# PCIE.net
KiCad netlist of a schematic drawn in Altium Designer
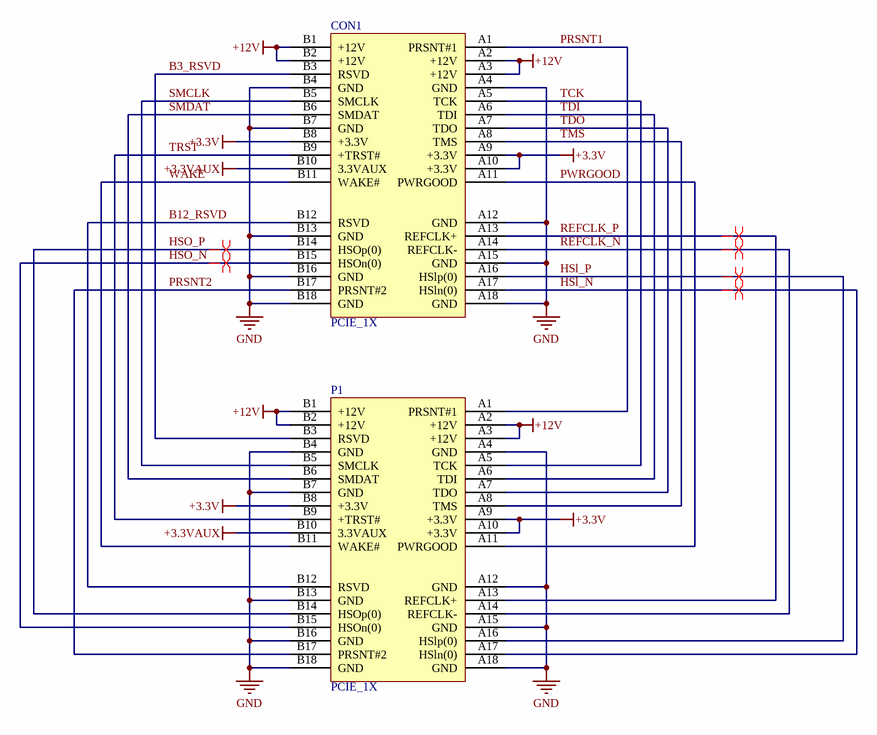
[diagram p0: PCIE.SchDoc]

(export (version "E")
  (design (tool "Eeschema 10.0.6"))
  (components
    (comp (ref "CON1") (value "PCIE_1X") (footprint "PCIE_1X_EDGE") (libsource (lib "PCIE") (part "PCIE_1X")))
    (comp (ref "P1") (value "PCIE_1X") (footprint "NWE18DHHN-T931") (libsource (lib "PCIE") (part "PCIE_1X")))
  )
  (nets
    (net (code "1") (name "+3.3V") (class "Default")
      (node (ref "CON1") (pin "A10") (pinfunction "+3.3V_A10") (pintype "power_in"))
      (node (ref "CON1") (pin "A9") (pinfunction "+3.3V_A9") (pintype "power_in"))
      (node (ref "CON1") (pin "B8") (pinfunction "+3.3V_B8") (pintype "power_in"))
      (node (ref "P1") (pin "A10") (pinfunction "+3.3V_A10") (pintype "power_in"))
      (node (ref "P1") (pin "A9") (pinfunction "+3.3V_A9") (pintype "power_in"))
      (node (ref "P1") (pin "B8") (pinfunction "+3.3V_B8") (pintype "power_in"))
    )
    (net (code "2") (name "+3.3VAUX") (class "Default")
      (node (ref "CON1") (pin "B10") (pinfunction "3.3VAUX_B10") (pintype "power_in"))
      (node (ref "P1") (pin "B10") (pinfunction "3.3VAUX_B10") (pintype "power_in"))
    )
    (net (code "3") (name "+12V") (class "Default")
      (node (ref "CON1") (pin "A2") (pinfunction "+12V_A2") (pintype "power_in"))
      (node (ref "CON1") (pin "A3") (pinfunction "+12V_A3") (pintype "power_in"))
      (node (ref "CON1") (pin "B1") (pinfunction "+12V_B1") (pintype "power_in"))
      (node (ref "CON1") (pin "B2") (pinfunction "+12V_B2") (pintype "power_in"))
      (node (ref "P1") (pin "A2") (pinfunction "+12V_A2") (pintype "power_in"))
      (node (ref "P1") (pin "A3") (pinfunction "+12V_A3") (pintype "power_in"))
      (node (ref "P1") (pin "B1") (pinfunction "+12V_B1") (pintype "power_in"))
      (node (ref "P1") (pin "B2") (pinfunction "+12V_B2") (pintype "power_in"))
    )
    (net (code "4") (name "/B3_RSVD") (class "Default")
      (node (ref "CON1") (pin "B3") (pinfunction "RSVD_B3") (pintype "power_in"))
      (node (ref "P1") (pin "B3") (pinfunction "RSVD_B3") (pintype "power_in"))
    )
    (net (code "5") (name "/B12_RSVD") (class "Default")
      (node (ref "CON1") (pin "B12") (pinfunction "RSVD_B12") (pintype "power_in"))
      (node (ref "P1") (pin "B12") (pinfunction "RSVD_B12") (pintype "power_in"))
    )
    (net (code "6") (name "/HSO_N") (class "Default")
      (node (ref "CON1") (pin "B15") (pinfunction "HSOn(0)_B15") (pintype "power_in"))
      (node (ref "P1") (pin "B15") (pinfunction "HSOn(0)_B15") (pintype "power_in"))
    )
    (net (code "7") (name "/HSO_P") (class "Default")
      (node (ref "CON1") (pin "B14") (pinfunction "HSOp(0)_B14") (pintype "power_in"))
      (node (ref "P1") (pin "B14") (pinfunction "HSOp(0)_B14") (pintype "power_in"))
    )
    (net (code "8") (name "/HSl_N") (class "Default")
      (node (ref "CON1") (pin "A17") (pinfunction "HSln(0)_A17") (pintype "power_in"))
      (node (ref "P1") (pin "A17") (pinfunction "HSln(0)_A17") (pintype "power_in"))
    )
    (net (code "9") (name "/HSl_P") (class "Default")
      (node (ref "CON1") (pin "A16") (pinfunction "HSlp(0)_A16") (pintype "power_in"))
      (node (ref "P1") (pin "A16") (pinfunction "HSlp(0)_A16") (pintype "power_in"))
    )
    (net (code "10") (name "/PRSNT1") (class "Default")
      (node (ref "CON1") (pin "A1") (pinfunction "PRSNT#1_A1") (pintype "power_in"))
      (node (ref "P1") (pin "A1") (pinfunction "PRSNT#1_A1") (pintype "power_in"))
    )
    (net (code "11") (name "/PRSNT2") (class "Default")
      (node (ref "CON1") (pin "B17") (pinfunction "PRSNT#2_B17") (pintype "power_in"))
      (node (ref "P1") (pin "B17") (pinfunction "PRSNT#2_B17") (pintype "power_in"))
    )
    (net (code "12") (name "/PWRGOOD") (class "Default")
      (node (ref "CON1") (pin "A11") (pinfunction "PWRGOOD_A11") (pintype "power_in"))
      (node (ref "P1") (pin "A11") (pinfunction "PWRGOOD_A11") (pintype "power_in"))
    )
    (net (code "13") (name "/REFCLK_N") (class "Default")
      (node (ref "CON1") (pin "A14") (pinfunction "REFCLK-_A14") (pintype "power_in"))
      (node (ref "P1") (pin "A14") (pinfunction "REFCLK-_A14") (pintype "power_in"))
    )
    (net (code "14") (name "/REFCLK_P") (class "Default")
      (node (ref "CON1") (pin "A13") (pinfunction "REFCLK+_A13") (pintype "power_in"))
      (node (ref "P1") (pin "A13") (pinfunction "REFCLK+_A13") (pintype "power_in"))
    )
    (net (code "15") (name "/SMCLK") (class "Default")
      (node (ref "CON1") (pin "B5") (pinfunction "SMCLK_B5") (pintype "power_in"))
      (node (ref "P1") (pin "B5") (pinfunction "SMCLK_B5") (pintype "power_in"))
    )
    (net (code "16") (name "/SMDAT") (class "Default")
      (node (ref "CON1") (pin "B6") (pinfunction "SMDAT_B6") (pintype "power_in"))
      (node (ref "P1") (pin "B6") (pinfunction "SMDAT_B6") (pintype "power_in"))
    )
    (net (code "17") (name "/TCK") (class "Default")
      (node (ref "CON1") (pin "A5") (pinfunction "TCK_A5") (pintype "power_in"))
      (node (ref "P1") (pin "A5") (pinfunction "TCK_A5") (pintype "power_in"))
    )
    (net (code "18") (name "/TDI") (class "Default")
      (node (ref "CON1") (pin "A6") (pinfunction "TDI_A6") (pintype "power_in"))
      (node (ref "P1") (pin "A6") (pinfunction "TDI_A6") (pintype "power_in"))
    )
    (net (code "19") (name "/TDO") (class "Default")
      (node (ref "CON1") (pin "A7") (pinfunction "TDO_A7") (pintype "power_in"))
      (node (ref "P1") (pin "A7") (pinfunction "TDO_A7") (pintype "power_in"))
    )
    (net (code "20") (name "/TMS") (class "Default")
      (node (ref "CON1") (pin "A8") (pinfunction "TMS_A8") (pintype "power_in"))
      (node (ref "P1") (pin "A8") (pinfunction "TMS_A8") (pintype "power_in"))
    )
    (net (code "21") (name "/TRST") (class "Default")
      (node (ref "CON1") (pin "B9") (pinfunction "+TRST#_B9") (pintype "power_in"))
      (node (ref "P1") (pin "B9") (pinfunction "+TRST#_B9") (pintype "power_in"))
    )
    (net (code "22") (name "/WAKE") (class "Default")
      (node (ref "CON1") (pin "B11") (pinfunction "WAKE#_B11") (pintype "power_in"))
      (node (ref "P1") (pin "B11") (pinfunction "WAKE#_B11") (pintype "power_in"))
    )
    (net (code "23") (name "GND") (class "Default")
      (node (ref "CON1") (pin "A12") (pinfunction "GND_A12") (pintype "power_in"))
      (node (ref "CON1") (pin "A15") (pinfunction "GND_A15") (pintype "power_in"))
      (node (ref "CON1") (pin "A18") (pinfunction "GND_A18") (pintype "power_in"))
      (node (ref "CON1") (pin "A4") (pinfunction "GND_A4") (pintype "power_in"))
      (node (ref "CON1") (pin "B13") (pinfunction "GND_B13") (pintype "power_in"))
      (node (ref "CON1") (pin "B16") (pinfunction "GND_B16") (pintype "power_in"))
      (node (ref "CON1") (pin "B18") (pinfunction "GND_B18") (pintype "power_in"))
      (node (ref "CON1") (pin "B4") (pinfunction "GND_B4") (pintype "power_in"))
      (node (ref "CON1") (pin "B7") (pinfunction "GND_B7") (pintype "power_in"))
      (node (ref "P1") (pin "A12") (pinfunction "GND_A12") (pintype "power_in"))
      (node (ref "P1") (pin "A15") (pinfunction "GND_A15") (pintype "power_in"))
      (node (ref "P1") (pin "A18") (pinfunction "GND_A18") (pintype "power_in"))
      (node (ref "P1") (pin "A4") (pinfunction "GND_A4") (pintype "power_in"))
      (node (ref "P1") (pin "B13") (pinfunction "GND_B13") (pintype "power_in"))
      (node (ref "P1") (pin "B16") (pinfunction "GND_B16") (pintype "power_in"))
      (node (ref "P1") (pin "B18") (pinfunction "GND_B18") (pintype "power_in"))
      (node (ref "P1") (pin "B4") (pinfunction "GND_B4") (pintype "power_in"))
      (node (ref "P1") (pin "B7") (pinfunction "GND_B7") (pintype "power_in"))
    )
  )
)
